# Power.net
KiCad netlist of a schematic drawn in Altium Designer
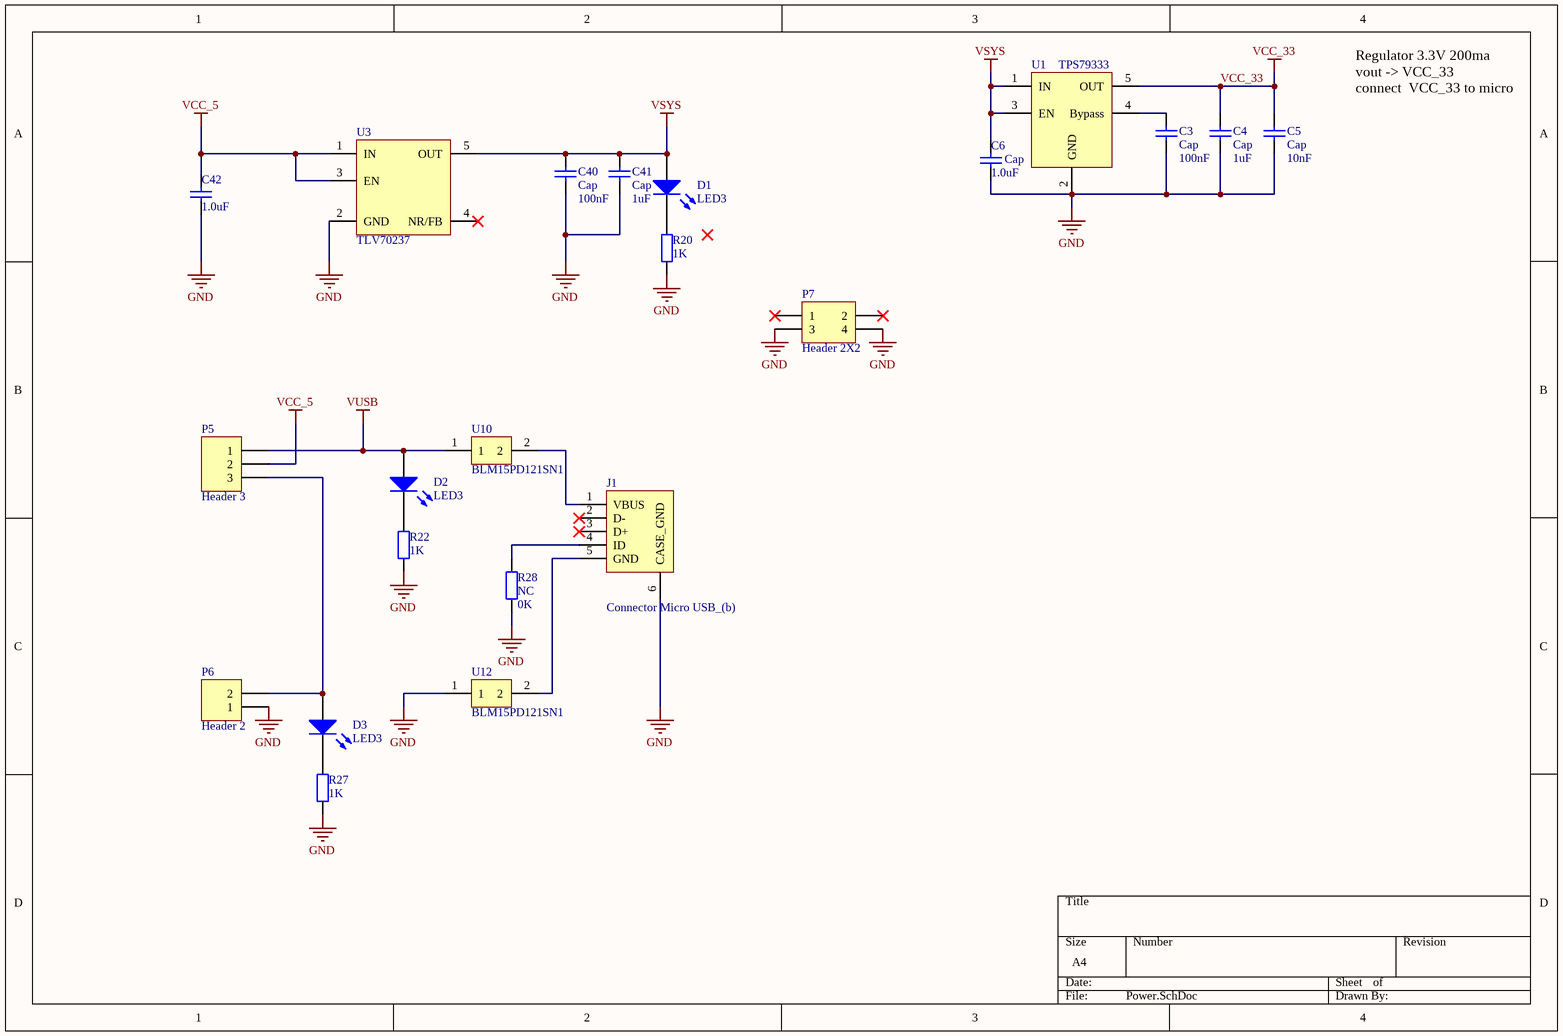
[diagram p0: Power.SchDoc]

(export (version "E")
  (design (tool "Eeschema 10.0.6"))
  (components
    (comp (ref "C3")
      (value "Cap")
      (footprint "Demo_Board_library_PCB:cap_0402_R - modified")
      (description "Capacitor")
      (fields (field (name "ALTIUM_VALUE") "100nF") (field (name "PUBLISHER") "Altium Limited"))
      (libsource (lib "Miscellaneous Devices") (part "Cap"))
    )
    (comp (ref "C4")
      (value "Cap")
      (footprint "Demo_Board_library_PCB:cap_0402_R - modified")
      (description "Capacitor")
      (fields (field (name "ALTIUM_VALUE") "1uF") (field (name "PUBLISHER") "Altium Limited"))
      (libsource (lib "Miscellaneous Devices") (part "Cap"))
    )
    (comp (ref "C5")
      (value "Cap")
      (footprint "Demo_Board_library_PCB:cap_0402_R - modified")
      (description "Capacitor")
      (fields (field (name "ALTIUM_VALUE") "10nF") (field (name "PUBLISHER") "Altium Limited"))
      (libsource (lib "Miscellaneous Devices") (part "Cap"))
    )
    (comp (ref "C6")
      (value "Cap")
      (footprint "Demo_Board_library_PCB:cap_0402_R - modified")
      (description "Capacitor")
      (fields (field (name "ALTIUM_VALUE") "1.0uF") (field (name "PUBLISHER") "Altium Limited"))
      (libsource (lib "Miscellaneous Devices") (part "Cap"))
    )
    (comp (ref "C40")
      (value "Cap")
      (footprint "Demo_Board_library_PCB:cap_0402_R - modified")
      (description "Capacitor")
      (fields (field (name "ALTIUM_VALUE") "100nF") (field (name "PUBLISHER") "Altium Limited"))
      (libsource (lib "Miscellaneous Devices") (part "Cap"))
    )
    (comp (ref "C41")
      (value "Cap")
      (footprint "Demo_Board_library_PCB:cap_0402_R - modified")
      (description "Capacitor")
      (fields (field (name "ALTIUM_VALUE") "1uF") (field (name "PUBLISHER") "Altium Limited"))
      (libsource (lib "Miscellaneous Devices") (part "Cap"))
    )
    (comp (ref "C42")
      (value "1.0uF")
      (footprint "Demo_Board_library_PCB:cap_0402_R - modified")
      (description "Capacitor")
      (fields (field (name "Comment") "Cap") (field (name "PUBLISHER") "Altium Limited"))
      (libsource (lib "Miscellaneous Devices") (part "Cap"))
    )
    (comp (ref "D1")
      (value "LED3")
      (footprint "0603")
      (description "Typical BLUE SiC LED")
      (fields (field (name "PUBLISHER") "Altium Limited"))
      (libsource (lib "Miscellaneous Devices") (part "LED3"))
    )
    (comp (ref "D2")
      (value "LED3")
      (footprint "0603")
      (description "Typical BLUE SiC LED")
      (fields (field (name "PUBLISHER") "Altium Limited"))
      (libsource (lib "Miscellaneous Devices") (part "LED3"))
    )
    (comp (ref "D3")
      (value "LED3")
      (footprint "0603")
      (description "Typical BLUE SiC LED")
      (fields (field (name "PUBLISHER") "Altium Limited"))
      (libsource (lib "Miscellaneous Devices") (part "LED3"))
    )
    (comp (ref "J1")
      (value "Connector Micro USB_(b)")
      (footprint "Demo_Board_library_PCB:CONNECTOR_MICRO_USB_B_TYPE")
      (description "CONNECTOR MICRO USB")
      (libsource (lib "Demo_Board_library_SCH") (part "Connector Micro USB_(b)"))
    )
    (comp (ref "P5")
      (value "Header 3")
      (footprint "HDR1X3")
      (description "Header, 3-Pin")
      (fields (field (name "PUBLISHER") "Altium Limited"))
      (libsource (lib "Miscellaneous Connectors") (part "Header 3"))
    )
    (comp (ref "P6")
      (value "Header 2")
      (footprint "HDR1X2")
      (description "Header, 2-Pin")
      (fields (field (name "PUBLISHER") "Altium Limited"))
      (libsource (lib "Miscellaneous Connectors") (part "Header 2"))
    )
    (comp (ref "P7")
      (value "Header 2X2")
      (footprint "HDR2X2")
      (description "Header, 2-Pin, Dual row")
      (fields (field (name "PUBLISHER") "Altium Limited"))
      (libsource (lib "Miscellaneous Connectors") (part "Header 2X2"))
    )
    (comp (ref "R20")
      (value "1K")
      (footprint "0603")
      (description "Resistor")
      (fields (field (name "Comment") "R") (field (name "PUBLISHER") "Altium Limited"))
      (libsource (lib "Miscellaneous Devices") (part "Res2"))
    )
    (comp (ref "R22")
      (value "1K")
      (footprint "0603")
      (description "Resistor")
      (fields (field (name "Comment") "R") (field (name "PUBLISHER") "Altium Limited"))
      (libsource (lib "Miscellaneous Devices") (part "Res2"))
    )
    (comp (ref "R27")
      (value "1K")
      (footprint "0603")
      (description "Resistor")
      (fields (field (name "Comment") "R") (field (name "PUBLISHER") "Altium Limited"))
      (libsource (lib "Miscellaneous Devices") (part "Res2"))
    )
    (comp (ref "R28")
      (value "NC")
      (footprint "cap_0402_R - modified")
      (description "Resistor")
      (fields (field (name "ALTIUM_VALUE") "0K") (field (name "PUBLISHER") "Altium Limited"))
      (libsource (lib "Miscellaneous Devices") (part "Res2"))
    )
    (comp (ref "U1")
      (value "TPS79333")
      (footprint "Demo_Board_library_PCB:SOT_23__DBV_(R - PDSO - G5)")
      (description "Regulator")
      (libsource (lib "Demo_Board_library_SCH") (part "TPS79333"))
    )
    (comp (ref "U3")
      (value "TLV70237")
      (footprint "Demo_Board_library_PCB:SOT23__DDC__(R - PDSO-  G5)")
      (description "Linear Regulator")
      (libsource (lib "Demo_Board_library_SCH") (part "TLV70237"))
    )
    (comp (ref "U10")
      (value "BLM15PD121SN1")
      (footprint "Demo_Board_library_PCB:BLM15PD121SN1")
      (libsource (lib "Demo_Board_library_SCH") (part "BLM15PD121SN1"))
    )
    (comp (ref "U12")
      (value "BLM15PD121SN1")
      (footprint "Demo_Board_library_PCB:BLM15PD121SN1")
      (libsource (lib "Demo_Board_library_SCH") (part "BLM15PD121SN1"))
    )
  )
  (nets
    (net (code "1") (name "GND") (class "Default")
      (node (ref "C3") (pin "1") (pinfunction "1_1") (pintype "passive"))
      (node (ref "C4") (pin "2") (pinfunction "2_2") (pintype "passive"))
      (node (ref "C40") (pin "1") (pinfunction "1_1") (pintype "passive"))
      (node (ref "C41") (pin "2") (pinfunction "2_2") (pintype "passive"))
      (node (ref "C42") (pin "1") (pinfunction "1_1") (pintype "passive"))
      (node (ref "C5") (pin "1") (pinfunction "1_1") (pintype "passive"))
      (node (ref "C6") (pin "1") (pinfunction "1_1") (pintype "passive"))
      (node (ref "J1") (pin "6") (pinfunction "CASE_GND_6") (pintype "passive"))
      (node (ref "P6") (pin "1") (pinfunction "1_1") (pintype "passive"))
      (node (ref "P7") (pin "3") (pinfunction "3_3") (pintype "passive"))
      (node (ref "P7") (pin "4") (pinfunction "4_4") (pintype "passive"))
      (node (ref "R20") (pin "1") (pinfunction "1_1") (pintype "passive"))
      (node (ref "R22") (pin "1") (pinfunction "1_1") (pintype "passive"))
      (node (ref "R27") (pin "1") (pinfunction "1_1") (pintype "passive"))
      (node (ref "R28") (pin "1") (pinfunction "1_1") (pintype "passive"))
      (node (ref "U1") (pin "2") (pinfunction "GND_2") (pintype "passive"))
      (node (ref "U12") (pin "1") (pinfunction "1_1") (pintype "passive"))
      (node (ref "U3") (pin "2") (pinfunction "GND_2") (pintype "passive"))
    )
    (net (code "2") (name "Net-(D1-K)") (class "Default")
      (node (ref "D1") (pin "2") (pinfunction "K_2") (pintype "passive"))
      (node (ref "R20") (pin "2") (pinfunction "2_2") (pintype "passive"))
    )
    (net (code "3") (name "Net-(D2-K)") (class "Default")
      (node (ref "D2") (pin "2") (pinfunction "K_2") (pintype "passive"))
      (node (ref "R22") (pin "2") (pinfunction "2_2") (pintype "passive"))
    )
    (net (code "4") (name "Net-(D3-A)") (class "Default")
      (node (ref "D3") (pin "1") (pinfunction "A_1") (pintype "passive"))
      (node (ref "P5") (pin "3") (pinfunction "3_3") (pintype "passive"))
      (node (ref "P6") (pin "2") (pinfunction "2_2") (pintype "passive"))
    )
    (net (code "5") (name "Net-(D3-K)") (class "Default")
      (node (ref "D3") (pin "2") (pinfunction "K_2") (pintype "passive"))
      (node (ref "R27") (pin "2") (pinfunction "2_2") (pintype "passive"))
    )
    (net (code "6") (name "Net-(J1-GND)") (class "Default")
      (node (ref "J1") (pin "5") (pinfunction "GND_5") (pintype "passive"))
      (node (ref "U12") (pin "2") (pinfunction "2_2") (pintype "passive"))
    )
    (net (code "7") (name "Net-(J1-ID)") (class "Default")
      (node (ref "J1") (pin "4") (pinfunction "ID_4") (pintype "passive"))
      (node (ref "R28") (pin "2") (pinfunction "2_2") (pintype "passive"))
    )
    (net (code "8") (name "Net-(J1-VBUS)") (class "Default")
      (node (ref "J1") (pin "1") (pinfunction "VBUS_1") (pintype "passive"))
      (node (ref "U10") (pin "2") (pinfunction "2_2") (pintype "passive"))
    )
    (net (code "9") (name "Net-(U1-Bypass)") (class "Default")
      (node (ref "C3") (pin "2") (pinfunction "2_2") (pintype "passive"))
      (node (ref "U1") (pin "4") (pinfunction "Bypass_4") (pintype "passive"))
    )
    (net (code "10") (name "VCC_5") (class "Default")
      (node (ref "C42") (pin "2") (pinfunction "2_2") (pintype "passive"))
      (node (ref "P5") (pin "2") (pinfunction "2_2") (pintype "passive"))
      (node (ref "U3") (pin "1") (pinfunction "IN_1") (pintype "passive"))
      (node (ref "U3") (pin "3") (pinfunction "EN_3") (pintype "passive"))
    )
    (net (code "11") (name "VCC_33") (class "Default")
      (node (ref "C4") (pin "1") (pinfunction "1_1") (pintype "passive"))
      (node (ref "C5") (pin "2") (pinfunction "2_2") (pintype "passive"))
      (node (ref "U1") (pin "5") (pinfunction "OUT_5") (pintype "passive"))
    )
    (net (code "12") (name "VSYS") (class "Default")
      (node (ref "C40") (pin "2") (pinfunction "2_2") (pintype "passive"))
      (node (ref "C41") (pin "1") (pinfunction "1_1") (pintype "passive"))
      (node (ref "C6") (pin "2") (pinfunction "2_2") (pintype "passive"))
      (node (ref "D1") (pin "1") (pinfunction "A_1") (pintype "passive"))
      (node (ref "U1") (pin "1") (pinfunction "IN_1") (pintype "passive"))
      (node (ref "U1") (pin "3") (pinfunction "EN_3") (pintype "passive"))
      (node (ref "U3") (pin "5") (pinfunction "OUT_5") (pintype "passive"))
    )
    (net (code "13") (name "VUSB") (class "Default")
      (node (ref "D2") (pin "1") (pinfunction "A_1") (pintype "passive"))
      (node (ref "P5") (pin "1") (pinfunction "1_1") (pintype "passive"))
      (node (ref "U10") (pin "1") (pinfunction "1_1") (pintype "passive"))
    )
    (net (code "14") (name "unconnected-(J1-D+-Pad3)") (class "Default")
      (node (ref "J1") (pin "3") (pinfunction "D+_3") (pintype "passive+no_connect"))
    )
    (net (code "15") (name "unconnected-(J1-D--Pad2)") (class "Default")
      (node (ref "J1") (pin "2") (pinfunction "D-_2") (pintype "passive+no_connect"))
    )
    (net (code "16") (name "unconnected-(P7-Pad1)") (class "Default")
      (node (ref "P7") (pin "1") (pinfunction "1_1") (pintype "passive+no_connect"))
    )
    (net (code "17") (name "unconnected-(P7-Pad2)") (class "Default")
      (node (ref "P7") (pin "2") (pinfunction "2_2") (pintype "passive+no_connect"))
    )
    (net (code "18") (name "unconnected-(U3-NR{slash}FB-Pad4)") (class "Default")
      (node (ref "U3") (pin "4") (pinfunction "NR/FB_4") (pintype "passive+no_connect"))
    )
  )
)
